# 16V2_EDA.net
KiCad netlist of a schematic drawn in EasyEDA Pro
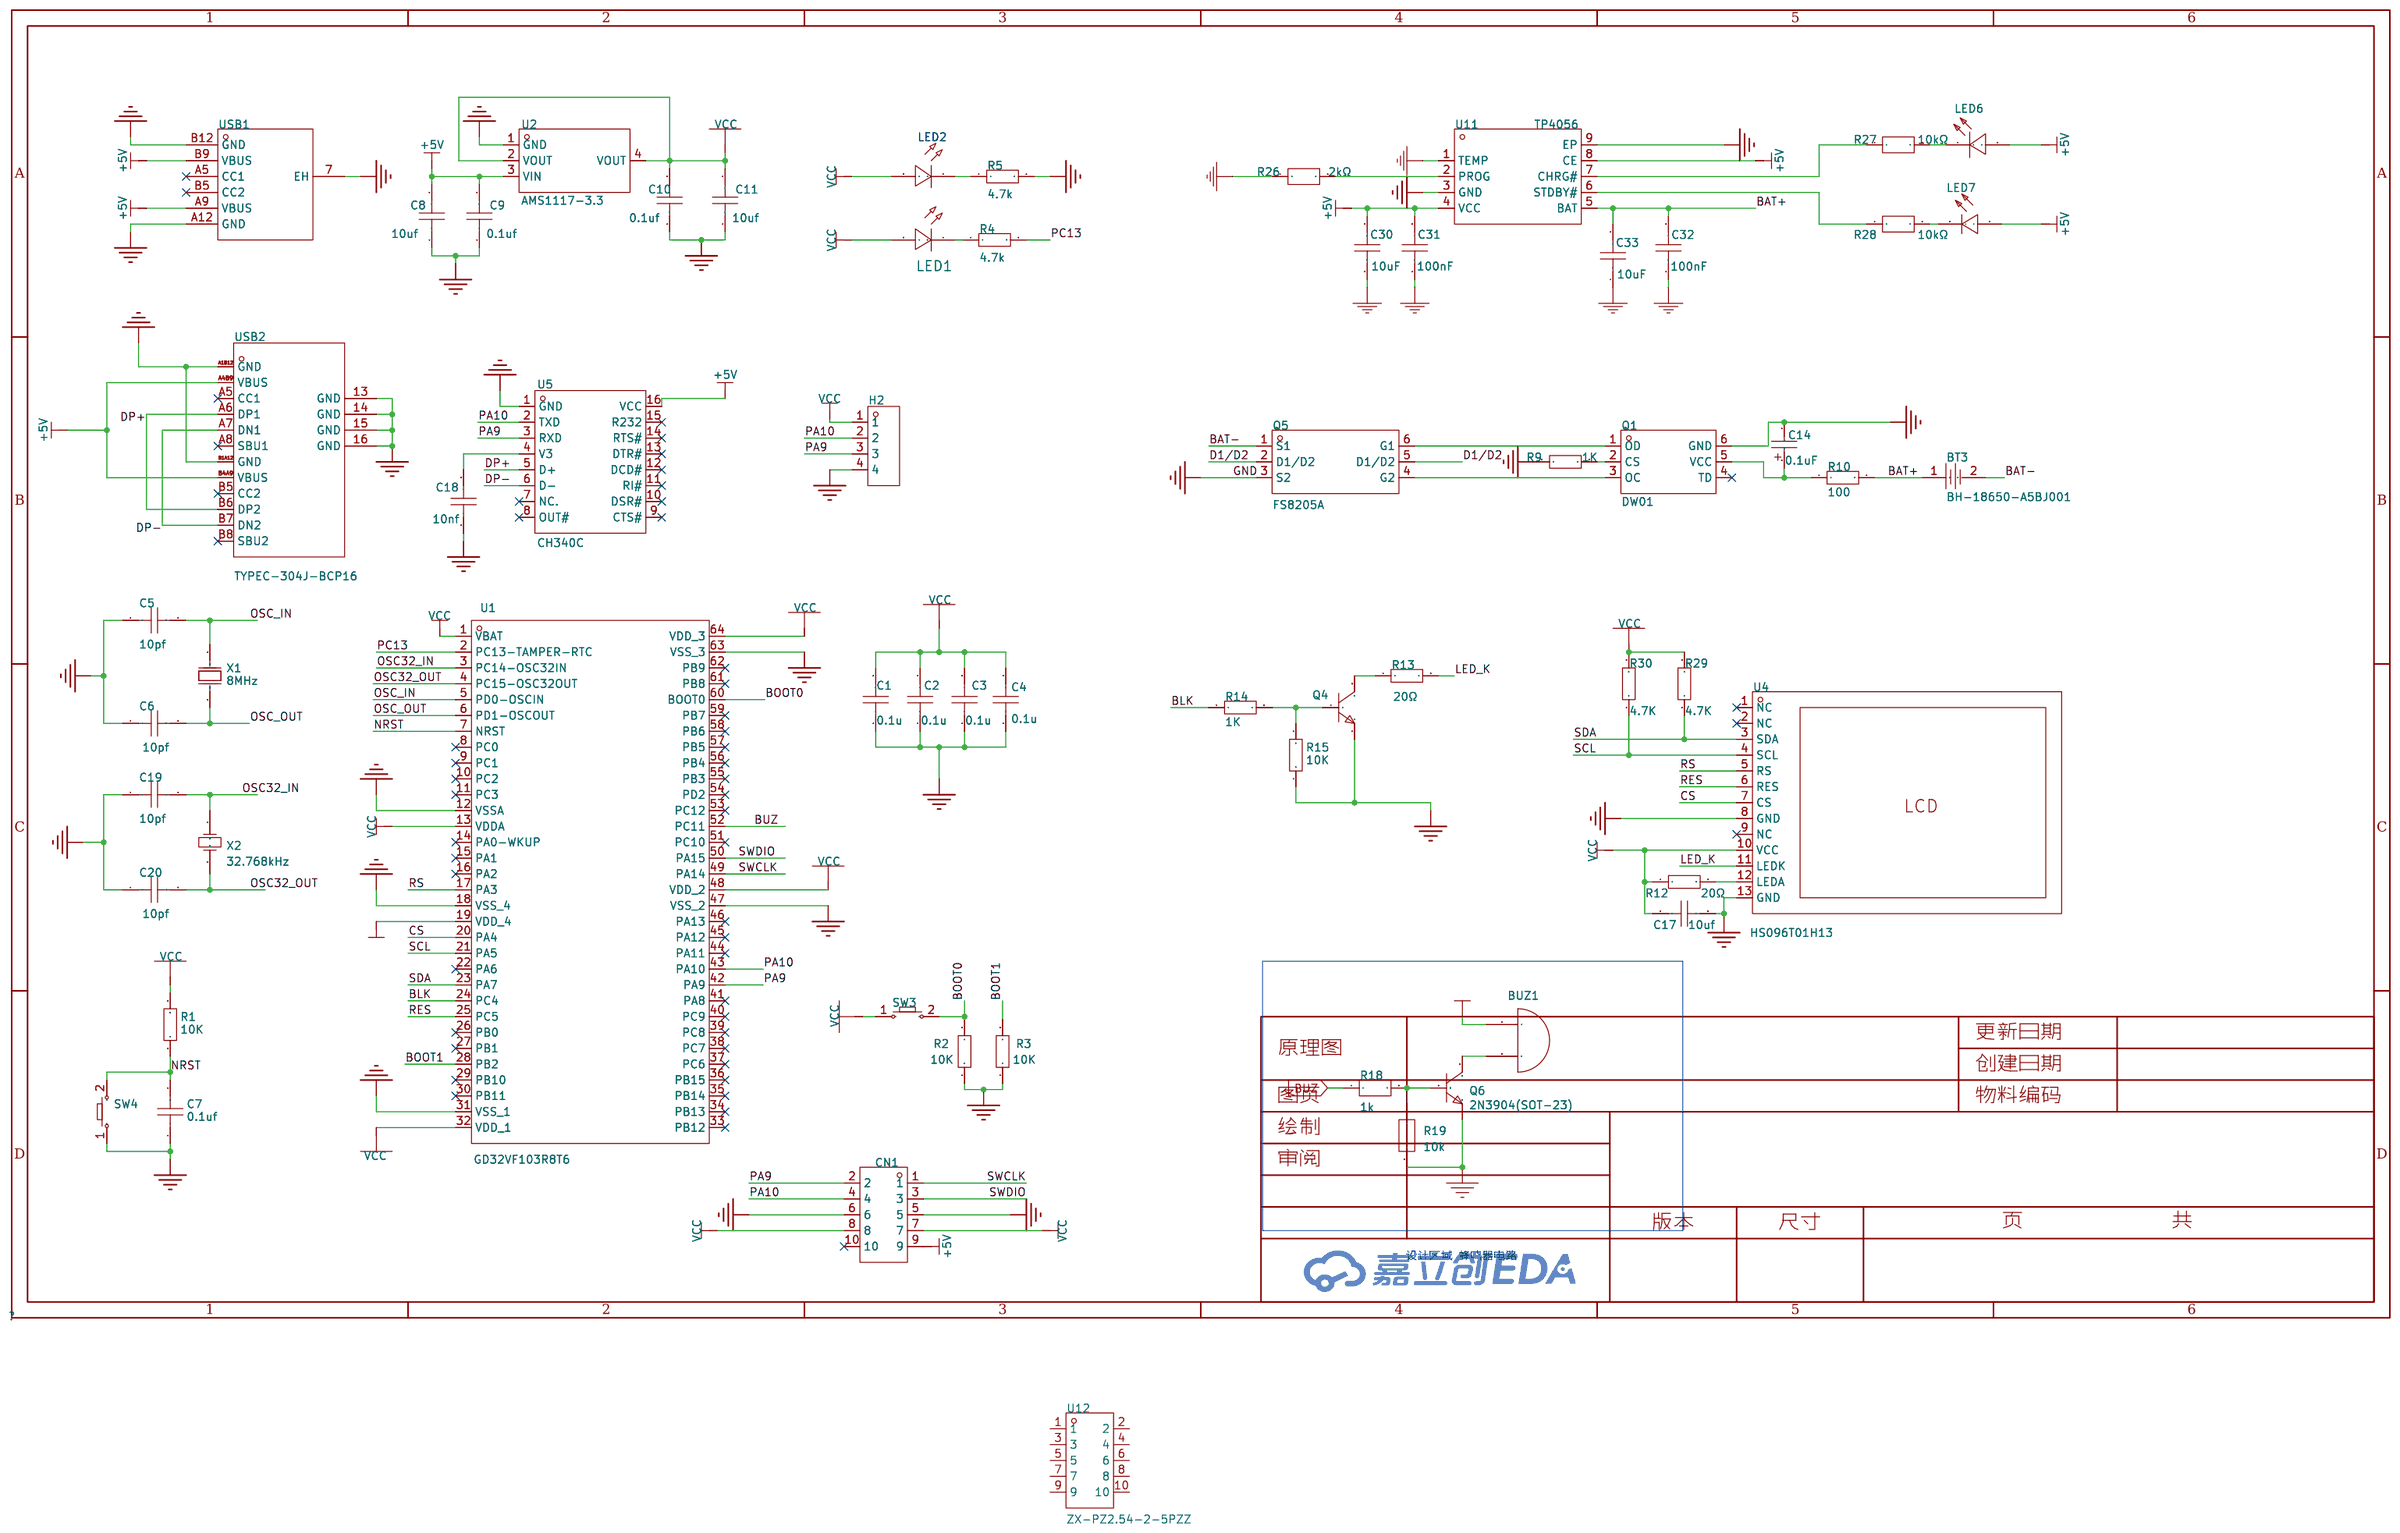
[diagram p0: schematic sheet]

(export (version "E")
  (design (tool "Eeschema 10.0.6"))
  (components
    (comp (ref "BT3")
      (value "BH-18650-A5BJ001")
      (footprint "easyedapro:BAT-TH_18650-A5BJ001")
      (description "BHNi DIP 适用电池18650电芯//电池底座/卧式DIP 电池盒/电池座 材质：PP  镀镍 ，")
      (fields (field (name "Manufacturer") "MYOUNG(美阳)"))
      (libsource (lib "easyedapro") (part "BH-18650-A5BJ001"))
    )
    (comp (ref "BUZ1") (value "BUZ1") (libsource (lib "easyedapro") (part "BUZ1")))
    (comp (ref "C1")
      (value "0.1u")
      (footprint "easyedapro:C0603")
      (libsource (lib "easyedapro") (part "capacitance"))
    )
    (comp (ref "C2")
      (value "0.1u")
      (footprint "easyedapro:C0603")
      (libsource (lib "easyedapro") (part "capacitance"))
    )
    (comp (ref "C3")
      (value "0.1u")
      (footprint "easyedapro:C0603")
      (libsource (lib "easyedapro") (part "capacitance"))
    )
    (comp (ref "C4")
      (value "0.1u")
      (footprint "easyedapro:C0603")
      (libsource (lib "easyedapro") (part "capacitance"))
    )
    (comp (ref "C5")
      (value "10pf")
      (footprint "easyedapro:C0603")
      (libsource (lib "easyedapro") (part "capacitance"))
    )
    (comp (ref "C6")
      (value "10pf")
      (footprint "easyedapro:C0603")
      (libsource (lib "easyedapro") (part "capacitance"))
    )
    (comp (ref "C7")
      (value "0.1uf")
      (footprint "easyedapro:C0603")
      (libsource (lib "easyedapro") (part "capacitance"))
    )
    (comp (ref "C8")
      (value "10uf")
      (footprint "easyedapro:C0603")
      (libsource (lib "easyedapro") (part "capacitance"))
    )
    (comp (ref "C9")
      (value "0.1uf")
      (footprint "easyedapro:C0603")
      (libsource (lib "easyedapro") (part "capacitance"))
    )
    (comp (ref "C10")
      (value "0.1uf")
      (footprint "easyedapro:C0603")
      (libsource (lib "easyedapro") (part "capacitance"))
    )
    (comp (ref "C11")
      (value "10uf")
      (footprint "easyedapro:C0603")
      (libsource (lib "easyedapro") (part "capacitance"))
    )
    (comp (ref "C14")
      (value "0.1uF")
      (footprint "easyedapro:C_Ele_SMD_3x5.4mm")
      (libsource (lib "easyedapro") (part "CAP"))
    )
    (comp (ref "C17")
      (value "10uf")
      (footprint "easyedapro:C0603")
      (libsource (lib "easyedapro") (part "capacitance"))
    )
    (comp (ref "C18")
      (value "10nf")
      (footprint "easyedapro:C0603")
      (libsource (lib "easyedapro") (part "capacitance"))
    )
    (comp (ref "C19")
      (value "10pf")
      (footprint "easyedapro:C0603")
      (libsource (lib "easyedapro") (part "capacitance"))
    )
    (comp (ref "C20")
      (value "10pf")
      (footprint "easyedapro:C0603")
      (libsource (lib "easyedapro") (part "capacitance"))
    )
    (comp (ref "C30")
      (value "10uF")
      (fields (field (name "Manufacturer") "SAMSUNG(三星)"))
      (libsource (lib "easyedapro") (part "10u"))
    )
    (comp (ref "C31")
      (value "100nF")
      (fields (field (name "Manufacturer") "YAGEO(国巨)"))
      (libsource (lib "easyedapro") (part "0.1u"))
    )
    (comp (ref "C32")
      (value "100nF")
      (fields (field (name "Manufacturer") "YAGEO(国巨)"))
      (libsource (lib "easyedapro") (part "0.1u"))
    )
    (comp (ref "C33")
      (value "10uF")
      (fields (field (name "Manufacturer") "SAMSUNG(三星)"))
      (libsource (lib "easyedapro") (part "10u"))
    )
    (comp (ref "CN1") (value "ZX-PZ2.54-2-5PZZ") (libsource (lib "easyedapro") (part "phd-2*5a_c2847737")))
    (comp (ref "H2")
      (value "2.54-1*4P反弯排针")
      (footprint "easyedapro:HDR-TH_4P-P2.54-H-M-W10.4")
      (fields (field (name "Manufacturer") "BOOMELE(博穆精密)"))
      (libsource (lib "easyedapro") (part "2.54-1*4P反弯排针"))
    )
    (comp (ref "LED1")
      (value "~")
      (footprint "easyedapro:LED_0603")
      (libsource (lib "easyedapro") (part "LED_R"))
    )
    (comp (ref "LED2")
      (value "~")
      (footprint "easyedapro:LED_0603")
      (libsource (lib "easyedapro") (part "LED_G"))
    )
    (comp (ref "LED6")
      (value "KT-0603R")
      (fields (field (name "Manufacturer") "KENTO"))
      (libsource (lib "easyedapro") (part "KT-0603R"))
    )
    (comp (ref "LED7") (value "NCD0603B1") (libsource (lib "easyedapro") (part "fc-da1608bk-470h10")))
    (comp (ref "Q1")
      (value "DW01")
      (footprint "easyedapro:SOT-23-6_L2.9-W1.6-P0.95-LS2.8-BR")
      (fields (field (name "Manufacturer") "Hottech(合科泰)"))
      (libsource (lib "easyedapro") (part "DW01"))
    )
    (comp (ref "Q4")
      (value "~")
      (footprint "easyedapro:S8050_SOT-23")
      (libsource (lib "easyedapro") (part "NPN"))
    )
    (comp (ref "Q5")
      (value "FS8205A")
      (footprint "easyedapro:SOT-23-6_L2.9-W1.6-P0.95-LS2.8-BR")
      (fields (field (name "Manufacturer") "TECH PUBLIC(台舟)"))
      (libsource (lib "easyedapro") (part "FS8205A_C2830320"))
    )
    (comp (ref "Q6")
      (value "2N3904(SOT-23)")
      (fields (field (name "Manufacturer Part") "2n3904S-RTK/PS") (field (name "Manufacturer") "KEC"))
      (libsource (lib "easyedapro") (part "2N3904(SOT-23)"))
    )
    (comp (ref "R1") (value "10K") (libsource (lib "easyedapro") (part "电阻")))
    (comp (ref "R2") (value "10K") (libsource (lib "easyedapro") (part "电阻")))
    (comp (ref "R3") (value "10K") (libsource (lib "easyedapro") (part "电阻")))
    (comp (ref "R4") (value "4.7k") (libsource (lib "easyedapro") (part "电阻")))
    (comp (ref "R5") (value "4.7k") (libsource (lib "easyedapro") (part "电阻")))
    (comp (ref "R9") (value "1K") (libsource (lib "easyedapro") (part "电阻")))
    (comp (ref "R10") (value "100") (libsource (lib "easyedapro") (part "电阻")))
    (comp (ref "R12") (value "20Ω") (libsource (lib "easyedapro") (part "电阻")))
    (comp (ref "R13") (value "20Ω") (libsource (lib "easyedapro") (part "电阻")))
    (comp (ref "R14") (value "1K") (libsource (lib "easyedapro") (part "电阻")))
    (comp (ref "R15") (value "10K") (libsource (lib "easyedapro") (part "电阻")))
    (comp (ref "R18") (value "1k") (libsource (lib "easyedapro") (part "1k")))
    (comp (ref "R19") (value "10k") (libsource (lib "easyedapro") (part "10k")))
    (comp (ref "R26")
      (value "2kΩ")
      (fields (field (name "Manufacturer") "UNI-ROYAL(厚声)"))
      (libsource (lib "easyedapro") (part "2k"))
    )
    (comp (ref "R27")
      (value "10kΩ")
      (fields (field (name "Manufacturer") "UNI-ROYAL(厚声)"))
      (libsource (lib "easyedapro") (part "10k"))
    )
    (comp (ref "R28")
      (value "10kΩ")
      (fields (field (name "Manufacturer") "UNI-ROYAL(厚声)"))
      (libsource (lib "easyedapro") (part "10k"))
    )
    (comp (ref "R29")
      (value "4.7K")
      (footprint "easyedapro:R0603")
      (libsource (lib "easyedapro") (part "电阻"))
    )
    (comp (ref "R30")
      (value "4.7K")
      (footprint "easyedapro:R0603")
      (libsource (lib "easyedapro") (part "电阻"))
    )
    (comp (ref "SW3")
      (value "~")
      (footprint "easyedapro:Key_SMD_3x4x2")
      (libsource (lib "easyedapro") (part "轻触按键x2"))
    )
    (comp (ref "SW4")
      (value "~")
      (footprint "easyedapro:Key_SMD_3x4x2")
      (libsource (lib "easyedapro") (part "轻触按键x2"))
    )
    (comp (ref "U1")
      (value "GD32VF103R8T6")
      (footprint "easyedapro:LQFP-64_L10.0-W10.0-P0.50-LS12.0-BL")
      (description "CPU内核:RISC-V;程序存储容量:64KB;RAM总容量:20KB;GPIO端口数量:51;工作电压范围:-;CPU最大主频:108MHz;程序存储器类型:FLASH;")
      (fields (field (name "Manufacturer") "GigaDevice(兆易创新)"))
      (libsource (lib "easyedapro") (part "GD32VF103R8T6"))
    )
    (comp (ref "U2")
      (value "AMS1117-3.3")
      (footprint "easyedapro:SOT-223-3_L6.5-W3.4-P2.30-LS7.0-BR")
      (description "输出类型:固定;最大输入电压:-;输出电压:3.3V;最大输出电流:1A;电源纹波抑制比(PSRR):72dB@(120Hz);输出极性:正极;")
      (fields (field (name "Manufacturer") "AMS"))
      (libsource (lib "easyedapro") (part "AMS1117-3.3"))
    )
    (comp (ref "U4")
      (value "HS096T01H13")
      (footprint "easyedapro:LCD-SMD_HS096T01H13")
      (description "主控芯片:ST7735;尺寸(inch):0.96;")
      (fields (field (name "Manufacturer") "HS(汉昇)"))
      (libsource (lib "easyedapro") (part "HS096T01H13"))
    )
    (comp (ref "U5")
      (value "CH340C")
      (footprint "easyedapro:SOP-16_L10.0-W3.9-P1.27-LS6.0-BL")
      (description "应用功能:收发器;接口协议:USB 2.0;数据速率:2Mbps;")
      (fields (field (name "Manufacturer") "WCH(南京沁恒)"))
      (libsource (lib "easyedapro") (part "CH340C"))
    )
    (comp (ref "U11")
      (value "TP4056")
      (fields (field (name "Manufacturer") "UMW(友台半导体)"))
      (libsource (lib "easyedapro") (part "TP4056_C725790"))
    )
    (comp (ref "U12")
      (value "ZX-PZ2.54-2-5PZZ")
      (footprint "easyedapro:HDR-TH_10P-P2.54-V-M-R2-C5-S2.54")
      (fields (field (name "Manufacturer") "Megastar(兆星)"))
      (libsource (lib "easyedapro") (part "ZX-PZ2.54-2-5PZZ"))
    )
    (comp (ref "USB1")
      (value "TYPE-C 6P")
      (footprint "easyedapro:TYPE-C-SMD_TYPE-C-6P")
      (description "连接器类型:Type-C;标准:-;公母:母;端口数量:1;触点数量:6P;安装方式:卧贴;额定电流 - 电源:-;工作温度范围:-40°C~+85°C;")
      (fields (field (name "Manufacturer") "SHOU HAN(首韩)"))
      (libsource (lib "easyedapro") (part "TYPE-C 6P"))
    )
    (comp (ref "USB2")
      (value "TYPEC-304J-BCP16")
      (footprint "easyedapro:USB-C-SMD_TYPEC-304J-BCP16")
      (fields (field (name "Manufacturer") "XUNPU(讯普)"))
      (libsource (lib "easyedapro") (part "TYPEC-304J-BCP16"))
    )
    (comp (ref "X1")
      (value "8MHz")
      (footprint "easyedapro:CRYSTAL-SMD_L11.5-W4.8-LS12.7")
      (description "晶振类型:贴片晶振;频率:8MHz;常温频差:±20ppm;外接负载电容:20pF;频率稳定度(全温):±30ppm;")
      (fields (field (name "Manufacturer Part") "X49SM8MSD2SC") (field (name "Manufacturer") "YXC(扬兴晶振)"))
      (libsource (lib "easyedapro") (part "X49SM8MSD2SC"))
    )
    (comp (ref "X2")
      (value "32.768kHz")
      (footprint "easyedapro:OSC-TH_BD3.1-P0.8-D0.3")
      (description "晶振类型:直插晶振;频率:32.768kHz;常温频差:±10ppm;外接负载电容:12.5pF;频率稳定度(全温):-;")
      (fields (field (name "Manufacturer Part") "X308032768KGB2SC") (field (name "Manufacturer") "YXC(扬兴晶振)"))
      (libsource (lib "easyedapro") (part "X308032768KGB2SC"))
    )
  )
  (nets
    (net (code "1") (name "+5V") (class "Default")
      (node (ref "C30") (pin "2") (pinfunction "2_2") (pintype "unspecified"))
      (node (ref "C31") (pin "2") (pinfunction "2_2") (pintype "unspecified"))
      (node (ref "C8") (pin "2") (pinfunction "2_2") (pintype "input"))
      (node (ref "C9") (pin "2") (pinfunction "2_2") (pintype "input"))
      (node (ref "CN1") (pin "9") (pinfunction "9_9") (pintype "unspecified"))
      (node (ref "LED6") (pin "2") (pinfunction "A_2") (pintype "unspecified"))
      (node (ref "LED7") (pin "2") (pinfunction "+_2") (pintype "input"))
      (node (ref "U11") (pin "4") (pinfunction "VCC_4") (pintype "unspecified"))
      (node (ref "U11") (pin "8") (pinfunction "CE_8") (pintype "unspecified"))
      (node (ref "U2") (pin "3") (pinfunction "VIN_3") (pintype "unspecified"))
      (node (ref "U5") (pin "16") (pinfunction "VCC_16") (pintype "unspecified"))
      (node (ref "USB1") (pin "A9") (pinfunction "VBUS_A9") (pintype "unspecified"))
      (node (ref "USB1") (pin "B9") (pinfunction "VBUS_B9") (pintype "unspecified"))
      (node (ref "USB2") (pin "A4B9") (pinfunction "VBUS_A4B9") (pintype "unspecified"))
      (node (ref "USB2") (pin "B4A9") (pinfunction "VBUS_B4A9") (pintype "unspecified"))
    )
    (net (code "2") (name "/BAT+") (class "Default")
      (node (ref "BT3") (pin "1") (pinfunction "1_1") (pintype "input"))
      (node (ref "C32") (pin "2") (pinfunction "2_2") (pintype "unspecified"))
      (node (ref "C33") (pin "2") (pinfunction "2_2") (pintype "unspecified"))
      (node (ref "R10") (pin "2") (pinfunction "2_2") (pintype "input"))
      (node (ref "U11") (pin "5") (pinfunction "BAT_5") (pintype "unspecified"))
    )
    (net (code "3") (name "/BAT-") (class "Default")
      (node (ref "BT3") (pin "2") (pinfunction "2_2") (pintype "input"))
      (node (ref "Q5") (pin "1") (pinfunction "S1_1") (pintype "unspecified"))
    )
    (net (code "4") (name "/BLK") (class "Default")
      (node (ref "R14") (pin "1") (pinfunction "1_1") (pintype "input"))
      (node (ref "U1") (pin "24") (pinfunction "PC4_24") (pintype "input"))
    )
    (net (code "5") (name "/BOOT0") (class "Default")
      (node (ref "R2") (pin "2") (pinfunction "2_2") (pintype "input"))
      (node (ref "SW3") (pin "2") (pinfunction "2_2") (pintype "input"))
      (node (ref "U1") (pin "60") (pinfunction "BOOT0_60") (pintype "input"))
    )
    (net (code "6") (name "/BOOT1") (class "Default")
      (node (ref "R3") (pin "2") (pinfunction "2_2") (pintype "input"))
      (node (ref "U1") (pin "28") (pinfunction "PB2_28") (pintype "input"))
    )
    (net (code "7") (name "/CS") (class "Default")
      (node (ref "U1") (pin "20") (pinfunction "PA4_20") (pintype "input"))
      (node (ref "U4") (pin "7") (pinfunction "CS_7") (pintype "unspecified"))
    )
    (net (code "8") (name "/D1{slash}D2") (class "Default")
      (node (ref "Q5") (pin "2") (pinfunction "D1/D2_2") (pintype "unspecified"))
      (node (ref "Q5") (pin "5") (pinfunction "D1/D2_5") (pintype "unspecified"))
    )
    (net (code "9") (name "/DP+") (class "Default")
      (node (ref "U5") (pin "5") (pinfunction "D+_5") (pintype "unspecified"))
      (node (ref "USB2") (pin "A6") (pinfunction "DP1_A6") (pintype "unspecified"))
      (node (ref "USB2") (pin "B6") (pinfunction "DP2_B6") (pintype "unspecified"))
    )
    (net (code "10") (name "/DP-") (class "Default")
      (node (ref "U5") (pin "6") (pinfunction "D-_6") (pintype "unspecified"))
      (node (ref "USB2") (pin "A7") (pinfunction "DN1_A7") (pintype "unspecified"))
      (node (ref "USB2") (pin "B7") (pinfunction "DN2_B7") (pintype "unspecified"))
    )
    (net (code "11") (name "/LED_K") (class "Default")
      (node (ref "R13") (pin "2") (pinfunction "2_2") (pintype "input"))
      (node (ref "U4") (pin "11") (pinfunction "LEDK_11") (pintype "unspecified"))
    )
    (net (code "12") (name "/NRST") (class "Default")
      (node (ref "C7") (pin "2") (pinfunction "2_2") (pintype "input"))
      (node (ref "R1") (pin "1") (pinfunction "1_1") (pintype "input"))
      (node (ref "SW4") (pin "2") (pinfunction "2_2") (pintype "input"))
      (node (ref "U1") (pin "7") (pinfunction "NRST_7") (pintype "input"))
    )
    (net (code "13") (name "/OSC32_IN") (class "Default")
      (node (ref "C19") (pin "2") (pinfunction "2_2") (pintype "input"))
      (node (ref "U1") (pin "3") (pinfunction "PC14-OSC32IN_3") (pintype "input"))
      (node (ref "X2") (pin "1") (pinfunction "OSC1_1") (pintype "unspecified"))
    )
    (net (code "14") (name "/OSC32_OUT") (class "Default")
      (node (ref "C20") (pin "2") (pinfunction "2_2") (pintype "input"))
      (node (ref "U1") (pin "4") (pinfunction "PC15-OSC32OUT_4") (pintype "input"))
      (node (ref "X2") (pin "2") (pinfunction "OSC2_2") (pintype "unspecified"))
    )
    (net (code "15") (name "/OSC_IN") (class "Default")
      (node (ref "C5") (pin "2") (pinfunction "2_2") (pintype "input"))
      (node (ref "U1") (pin "5") (pinfunction "PD0-OSCIN_5") (pintype "input"))
      (node (ref "X1") (pin "1") (pinfunction "OSC1_1") (pintype "input"))
    )
    (net (code "16") (name "/OSC_OUT") (class "Default")
      (node (ref "C6") (pin "2") (pinfunction "2_2") (pintype "input"))
      (node (ref "U1") (pin "6") (pinfunction "PD1-OSCOUT_6") (pintype "input"))
      (node (ref "X1") (pin "2") (pinfunction "OSC2_2") (pintype "input"))
    )
    (net (code "17") (name "/PA9") (class "Default")
      (node (ref "CN1") (pin "2") (pinfunction "2_2") (pintype "unspecified"))
      (node (ref "H2") (pin "3") (pinfunction "3_3") (pintype "unspecified"))
      (node (ref "U1") (pin "42") (pinfunction "PA9_42") (pintype "input"))
      (node (ref "U5") (pin "3") (pinfunction "RXD_3") (pintype "unspecified"))
    )
    (net (code "18") (name "/PA10") (class "Default")
      (node (ref "CN1") (pin "4") (pinfunction "4_4") (pintype "unspecified"))
      (node (ref "H2") (pin "2") (pinfunction "2_2") (pintype "unspecified"))
      (node (ref "U1") (pin "43") (pinfunction "PA10_43") (pintype "input"))
      (node (ref "U5") (pin "2") (pinfunction "TXD_2") (pintype "unspecified"))
    )
    (net (code "19") (name "/PC13") (class "Default")
      (node (ref "R4") (pin "2") (pinfunction "2_2") (pintype "input"))
      (node (ref "U1") (pin "2") (pinfunction "PC13-TAMPER-RTC_2") (pintype "input"))
    )
    (net (code "20") (name "/RES") (class "Default")
      (node (ref "U1") (pin "25") (pinfunction "PC5_25") (pintype "input"))
      (node (ref "U4") (pin "6") (pinfunction "RES_6") (pintype "unspecified"))
    )
    (net (code "21") (name "/RS") (class "Default")
      (node (ref "U1") (pin "17") (pinfunction "PA3_17") (pintype "input"))
      (node (ref "U4") (pin "5") (pinfunction "RS_5") (pintype "unspecified"))
    )
    (net (code "22") (name "/SCL") (class "Default")
      (node (ref "R30") (pin "1") (pinfunction "1_1") (pintype "input"))
      (node (ref "U1") (pin "21") (pinfunction "PA5_21") (pintype "input"))
      (node (ref "U4") (pin "4") (pinfunction "SCL_4") (pintype "unspecified"))
    )
    (net (code "23") (name "/SDA") (class "Default")
      (node (ref "R29") (pin "1") (pinfunction "1_1") (pintype "input"))
      (node (ref "U1") (pin "23") (pinfunction "PA7_23") (pintype "input"))
      (node (ref "U4") (pin "3") (pinfunction "SDA_3") (pintype "unspecified"))
    )
    (net (code "24") (name "/SWCLK") (class "Default")
      (node (ref "CN1") (pin "1") (pinfunction "1_1") (pintype "unspecified"))
      (node (ref "U1") (pin "49") (pinfunction "PA14_49") (pintype "input"))
    )
    (net (code "25") (name "/SWDIO") (class "Default")
      (node (ref "CN1") (pin "3") (pinfunction "3_3") (pintype "unspecified"))
      (node (ref "U1") (pin "50") (pinfunction "PA15_50") (pintype "input"))
    )
    (net (code "26") (name "BUZ") (class "Default")
      (node (ref "R18") (pin "1") (pinfunction "1_1") (pintype "input"))
      (node (ref "U1") (pin "52") (pinfunction "PC11_52") (pintype "input"))
    )
    (net (code "27") (name "GND") (class "Default")
      (node (ref "C1") (pin "1") (pinfunction "1_1") (pintype "input"))
      (node (ref "C10") (pin "1") (pinfunction "1_1") (pintype "input"))
      (node (ref "C11") (pin "1") (pinfunction "1_1") (pintype "input"))
      (node (ref "C14") (pin "2") (pinfunction "2_2") (pintype "input"))
      (node (ref "C17") (pin "2") (pinfunction "2_2") (pintype "input"))
      (node (ref "C18") (pin "1") (pinfunction "1_1") (pintype "input"))
      (node (ref "C19") (pin "1") (pinfunction "1_1") (pintype "input"))
      (node (ref "C2") (pin "1") (pinfunction "1_1") (pintype "input"))
      (node (ref "C20") (pin "1") (pinfunction "1_1") (pintype "input"))
      (node (ref "C3") (pin "1") (pinfunction "1_1") (pintype "input"))
      (node (ref "C30") (pin "1") (pinfunction "1_1") (pintype "unspecified"))
      (node (ref "C31") (pin "1") (pinfunction "1_1") (pintype "unspecified"))
      (node (ref "C32") (pin "1") (pinfunction "1_1") (pintype "unspecified"))
      (node (ref "C33") (pin "1") (pinfunction "1_1") (pintype "unspecified"))
      (node (ref "C4") (pin "1") (pinfunction "1_1") (pintype "input"))
      (node (ref "C5") (pin "1") (pinfunction "1_1") (pintype "input"))
      (node (ref "C6") (pin "1") (pinfunction "1_1") (pintype "input"))
      (node (ref "C7") (pin "1") (pinfunction "1_1") (pintype "input"))
      (node (ref "C8") (pin "1") (pinfunction "1_1") (pintype "input"))
      (node (ref "C9") (pin "1") (pinfunction "1_1") (pintype "input"))
      (node (ref "CN1") (pin "5") (pinfunction "5_5") (pintype "unspecified"))
      (node (ref "CN1") (pin "6") (pinfunction "6_6") (pintype "unspecified"))
      (node (ref "H2") (pin "4") (pinfunction "4_4") (pintype "unspecified"))
      (node (ref "Q1") (pin "6") (pinfunction "GND_6") (pintype "input"))
      (node (ref "Q4") (pin "2") (pinfunction "2_2") (pintype "unspecified"))
      (node (ref "Q5") (pin "3") (pinfunction "S2_3") (pintype "unspecified"))
      (node (ref "Q6") (pin "1") (pinfunction "E_1") (pintype "input"))
      (node (ref "R15") (pin "1") (pinfunction "1_1") (pintype "input"))
      (node (ref "R19") (pin "2") (pinfunction "2_2") (pintype "unspecified"))
      (node (ref "R2") (pin "1") (pinfunction "1_1") (pintype "input"))
      (node (ref "R26") (pin "1") (pinfunction "1_1") (pintype "unspecified"))
      (node (ref "R3") (pin "1") (pinfunction "1_1") (pintype "input"))
      (node (ref "R5") (pin "2") (pinfunction "2_2") (pintype "input"))
      (node (ref "R9") (pin "1") (pinfunction "1_1") (pintype "input"))
      (node (ref "SW4") (pin "1") (pinfunction "1_1") (pintype "input"))
      (node (ref "U1") (pin "12") (pinfunction "VSSA_12") (pintype "input"))
      (node (ref "U1") (pin "18") (pinfunction "VSS_4_18") (pintype "input"))
      (node (ref "U1") (pin "31") (pinfunction "VSS_1_31") (pintype "input"))
      (node (ref "U1") (pin "47") (pinfunction "VSS_2_47") (pintype "input"))
      (node (ref "U1") (pin "63") (pinfunction "VSS_3_63") (pintype "input"))
      (node (ref "U11") (pin "1") (pinfunction "TEMP_1") (pintype "unspecified"))
      (node (ref "U11") (pin "3") (pinfunction "GND_3") (pintype "unspecified"))
      (node (ref "U11") (pin "9") (pinfunction "EP_9") (pintype "unspecified"))
      (node (ref "U2") (pin "1") (pinfunction "GND_1") (pintype "unspecified"))
      (node (ref "U4") (pin "13") (pinfunction "GND_13") (pintype "unspecified"))
      (node (ref "U4") (pin "8") (pinfunction "GND_8") (pintype "unspecified"))
      (node (ref "U5") (pin "1") (pinfunction "GND_1") (pintype "unspecified"))
      (node (ref "USB1") (pin "7") (pinfunction "EH_7") (pintype "unspecified"))
      (node (ref "USB1") (pin "A12") (pinfunction "GND_A12") (pintype "unspecified"))
      (node (ref "USB1") (pin "B12") (pinfunction "GND_B12") (pintype "unspecified"))
      (node (ref "USB2") (pin "13") (pinfunction "GND_13") (pintype "unspecified"))
      (node (ref "USB2") (pin "14") (pinfunction "GND_14") (pintype "unspecified"))
      (node (ref "USB2") (pin "15") (pinfunction "GND_15") (pintype "unspecified"))
      (node (ref "USB2") (pin "16") (pinfunction "GND_16") (pintype "unspecified"))
      (node (ref "USB2") (pin "A1B12") (pinfunction "GND_A1B12") (pintype "unspecified"))
      (node (ref "USB2") (pin "B1A12") (pinfunction "GND_B1A12") (pintype "unspecified"))
    )
    (net (code "28") (name "Net-(BUZ1-B)") (class "Default")
      (node (ref "BUZ1") (pin "2") (pinfunction "B_2") (pintype "input"))
      (node (ref "Q6") (pin "3") (pinfunction "C_3") (pintype "input"))
    )
    (net (code "29") (name "Net-(LED1-C)") (class "Default")
      (node (ref "LED1") (pin "1") (pinfunction "C_1") (pintype "input"))
      (node (ref "R4") (pin "1") (pinfunction "1_1") (pintype "input"))
    )
    (net (code "30") (name "Net-(LED2-C)") (class "Default")
      (node (ref "LED2") (pin "1") (pinfunction "C_1") (pintype "input"))
      (node (ref "R5") (pin "1") (pinfunction "1_1") (pintype "input"))
    )
    (net (code "31") (name "Net-(LED6-K)") (class "Default")
      (node (ref "LED6") (pin "1") (pinfunction "K_1") (pintype "unspecified"))
      (node (ref "R27") (pin "2") (pinfunction "2_2") (pintype "unspecified"))
    )
    (net (code "32") (name "Net-(LED7--)") (class "Default")
      (node (ref "LED7") (pin "1") (pinfunction "-_1") (pintype "input"))
      (node (ref "R28") (pin "2") (pinfunction "2_2") (pintype "unspecified"))
    )
    (net (code "33") (name "Net-(Q1-CS)") (class "Default")
      (node (ref "Q1") (pin "2") (pinfunction "CS_2") (pintype "input"))
      (node (ref "R9") (pin "2") (pinfunction "2_2") (pintype "input"))
    )
    (net (code "34") (name "Net-(Q1-OC)") (class "Default")
      (node (ref "Q1") (pin "3") (pinfunction "OC_3") (pintype "input"))
      (node (ref "Q5") (pin "4") (pinfunction "G2_4") (pintype "unspecified"))
    )
    (net (code "35") (name "Net-(Q1-OD)") (class "Default")
      (node (ref "Q1") (pin "1") (pinfunction "OD_1") (pintype "input"))
      (node (ref "Q5") (pin "6") (pinfunction "G1_6") (pintype "unspecified"))
    )
    (net (code "36") (name "Net-(Q1-VCC)") (class "Default")
      (node (ref "C14") (pin "1") (pinfunction "1_1") (pintype "input"))
      (node (ref "Q1") (pin "5") (pinfunction "VCC_5") (pintype "input"))
      (node (ref "R10") (pin "1") (pinfunction "1_1") (pintype "input"))
    )
    (net (code "37") (name "Net-(Q4-Pad1)") (class "Default")
      (node (ref "Q4") (pin "1") (pinfunction "1_1") (pintype "unspecified"))
      (node (ref "R14") (pin "2") (pinfunction "2_2") (pintype "input"))
      (node (ref "R15") (pin "2") (pinfunction "2_2") (pintype "input"))
    )
    (net (code "38") (name "Net-(Q4-Pad3)") (class "Default")
      (node (ref "Q4") (pin "3") (pinfunction "3_3") (pintype "unspecified"))
      (node (ref "R13") (pin "1") (pinfunction "1_1") (pintype "input"))
    )
    (net (code "39") (name "Net-(Q6-B)") (class "Default")
      (node (ref "Q6") (pin "2") (pinfunction "B_2") (pintype "input"))
      (node (ref "R18") (pin "2") (pinfunction "2_2") (pintype "input"))
      (node (ref "R19") (pin "1") (pinfunction "1_1") (pintype "unspecified"))
    )
    (net (code "40") (name "Net-(U4-LEDA)") (class "Default")
      (node (ref "R12") (pin "2") (pinfunction "2_2") (pintype "input"))
      (node (ref "U4") (pin "12") (pinfunction "LEDA_12") (pintype "unspecified"))
    )
    (net (code "41") (name "Net-(U5-V3)") (class "Default")
      (node (ref "C18") (pin "2") (pinfunction "2_2") (pintype "input"))
      (node (ref "U5") (pin "4") (pinfunction "V3_4") (pintype "unspecified"))
    )
    (net (code "42") (name "Net-(U11-CHRG#)") (class "Default")
      (node (ref "R27") (pin "1") (pinfunction "1_1") (pintype "unspecified"))
      (node (ref "U11") (pin "7") (pinfunction "CHRG#_7") (pintype "unspecified"))
    )
    (net (code "43") (name "Net-(U11-PROG)") (class "Default")
      (node (ref "R26") (pin "2") (pinfunction "2_2") (pintype "unspecified"))
      (node (ref "U11") (pin "2") (pinfunction "PROG_2") (pintype "unspecified"))
    )
    (net (code "44") (name "Net-(U11-STDBY#)") (class "Default")
      (node (ref "R28") (pin "1") (pinfunction "1_1") (pintype "unspecified"))
      (node (ref "U11") (pin "6") (pinfunction "STDBY#_6") (pintype "unspecified"))
    )
    (net (code "45") (name "VCC") (class "Default")
      (node (ref "BUZ1") (pin "1") (pinfunction "A_1") (pintype "input"))
      (node (ref "C1") (pin "2") (pinfunction "2_2") (pintype "input"))
      (node (ref "C10") (pin "2") (pinfunction "2_2") (pintype "input"))
      (node (ref "C11") (pin "2") (pinfunction "2_2") (pintype "input"))
      (node (ref "C17") (pin "1") (pinfunction "1_1") (pintype "input"))
      (node (ref "C2") (pin "2") (pinfunction "2_2") (pintype "input"))
      (node (ref "C3") (pin "2") (pinfunction "2_2") (pintype "input"))
      (node (ref "C4") (pin "2") (pinfunction "2_2") (pintype "input"))
      (node (ref "CN1") (pin "7") (pinfunction "7_7") (pintype "unspecified"))
      (node (ref "CN1") (pin "8") (pinfunction "8_8") (pintype "unspecified"))
      (node (ref "H2") (pin "1") (pinfunction "1_1") (pintype "unspecified"))
      (node (ref "LED1") (pin "2") (pinfunction "A_2") (pintype "input"))
      (node (ref "LED2") (pin "2") (pinfunction "A_2") (pintype "input"))
      (node (ref "R1") (pin "2") (pinfunction "2_2") (pintype "input"))
      (node (ref "R12") (pin "1") (pinfunction "1_1") (pintype "input"))
      (node (ref "R29") (pin "2") (pinfunction "2_2") (pintype "input"))
      (node (ref "R30") (pin "2") (pinfunction "2_2") (pintype "input"))
      (node (ref "SW3") (pin "1") (pinfunction "1_1") (pintype "input"))
      (node (ref "U1") (pin "1") (pinfunction "VBAT_1") (pintype "input"))
      (node (ref "U1") (pin "13") (pinfunction "VDDA_13") (pintype "input"))
      (node (ref "U1") (pin "19") (pinfunction "VDD_4_19") (pintype "input"))
      (node (ref "U1") (pin "32") (pinfunction "VDD_1_32") (pintype "input"))
      (node (ref "U1") (pin "48") (pinfunction "VDD_2_48") (pintype "input"))
      (node (ref "U1") (pin "64") (pinfunction "VDD_3_64") (pintype "input"))
      (node (ref "U2") (pin "2") (pinfunction "VOUT_2") (pintype "unspecified"))
      (node (ref "U2") (pin "4") (pinfunction "VOUT_4") (pintype "unspecified"))
      (node (ref "U4") (pin "10") (pinfunction "VCC_10") (pintype "unspecified"))
    )
    (net (code "46") (name "unconnected-(CN1-Pad10)") (class "Default")
      (node (ref "CN1") (pin "10") (pinfunction "10_10") (pintype "unspecified+no_connect"))
    )
    (net (code "47") (name "unconnected-(Q1-TD-Pad4)") (class "Default")
      (node (ref "Q1") (pin "4") (pinfunction "TD_4") (pintype "input+no_connect"))
    )
    (net (code "48") (name "unconnected-(U1-PA0-WKUP-Pad14)") (class "Default")
      (node (ref "U1") (pin "14") (pinfunction "PA0-WKUP_14") (pintype "input+no_connect"))
    )
    (net (code "49") (name "unconnected-(U1-PA1-Pad15)") (class "Default")
      (node (ref "U1") (pin "15") (pinfunction "PA1_15") (pintype "input+no_connect"))
    )
    (net (code "50") (name "unconnected-(U1-PA2-Pad16)") (class "Default")
      (node (ref "U1") (pin "16") (pinfunction "PA2_16") (pintype "input+no_connect"))
    )
    (net (code "51") (name "unconnected-(U1-PA6-Pad22)") (class "Default")
      (node (ref "U1") (pin "22") (pinfunction "PA6_22") (pintype "input+no_connect"))
    )
    (net (code "52") (name "unconnected-(U1-PA8-Pad41)") (class "Default")
      (node (ref "U1") (pin "41") (pinfunction "PA8_41") (pintype "input+no_connect"))
    )
    (net (code "53") (name "unconnected-(U1-PA11-Pad44)") (class "Default")
      (node (ref "U1") (pin "44") (pinfunction "PA11_44") (pintype "input+no_connect"))
    )
    (net (code "54") (name "unconnected-(U1-PA12-Pad45)") (class "Default")
      (node (ref "U1") (pin "45") (pinfunction "PA12_45") (pintype "input+no_connect"))
    )
    (net (code "55") (name "unconnected-(U1-PA13-Pad46)") (class "Default")
      (node (ref "U1") (pin "46") (pinfunction "PA13_46") (pintype "input+no_connect"))
    )
    (net (code "56") (name "unconnected-(U1-PB0-Pad26)") (class "Default")
      (node (ref "U1") (pin "26") (pinfunction "PB0_26") (pintype "input+no_connect"))
    )
    (net (code "57") (name "unconnected-(U1-PB1-Pad27)") (class "Default")
      (node (ref "U1") (pin "27") (pinfunction "PB1_27") (pintype "input+no_connect"))
    )
    (net (code "58") (name "unconnected-(U1-PB3-Pad55)") (class "Default")
      (node (ref "U1") (pin "55") (pinfunction "PB3_55") (pintype "input+no_connect"))
    )
    (net (code "59") (name "unconnected-(U1-PB4-Pad56)") (class "Default")
      (node (ref "U1") (pin "56") (pinfunction "PB4_56") (pintype "input+no_connect"))
    )
    (net (code "60") (name "unconnected-(U1-PB5-Pad57)") (class "Default")
      (node (ref "U1") (pin "57") (pinfunction "PB5_57") (pintype "input+no_connect"))
    )
    (net (code "61") (name "unconnected-(U1-PB6-Pad58)") (class "Default")
      (node (ref "U1") (pin "58") (pinfunction "PB6_58") (pintype "input+no_connect"))
    )
    (net (code "62") (name "unconnected-(U1-PB7-Pad59)") (class "Default")
      (node (ref "U1") (pin "59") (pinfunction "PB7_59") (pintype "input+no_connect"))
    )
    (net (code "63") (name "unconnected-(U1-PB8-Pad61)") (class "Default")
      (node (ref "U1") (pin "61") (pinfunction "PB8_61") (pintype "input+no_connect"))
    )
    (net (code "64") (name "unconnected-(U1-PB9-Pad62)") (class "Default")
      (node (ref "U1") (pin "62") (pinfunction "PB9_62") (pintype "input+no_connect"))
    )
    (net (code "65") (name "unconnected-(U1-PB10-Pad29)") (class "Default")
      (node (ref "U1") (pin "29") (pinfunction "PB10_29") (pintype "input+no_connect"))
    )
    (net (code "66") (name "unconnected-(U1-PB11-Pad30)") (class "Default")
      (node (ref "U1") (pin "30") (pinfunction "PB11_30") (pintype "input+no_connect"))
    )
    (net (code "67") (name "unconnected-(U1-PB12-Pad33)") (class "Default")
      (node (ref "U1") (pin "33") (pinfunction "PB12_33") (pintype "input+no_connect"))
    )
    (net (code "68") (name "unconnected-(U1-PB13-Pad34)") (class "Default")
      (node (ref "U1") (pin "34") (pinfunction "PB13_34") (pintype "input+no_connect"))
    )
    (net (code "69") (name "unconnected-(U1-PB14-Pad35)") (class "Default")
      (node (ref "U1") (pin "35") (pinfunction "PB14_35") (pintype "input+no_connect"))
    )
    (net (code "70") (name "unconnected-(U1-PB15-Pad36)") (class "Default")
      (node (ref "U1") (pin "36") (pinfunction "PB15_36") (pintype "input+no_connect"))
    )
    (net (code "71") (name "unconnected-(U1-PC0-Pad8)") (class "Default")
      (node (ref "U1") (pin "8") (pinfunction "PC0_8") (pintype "input+no_connect"))
    )
    (net (code "72") (name "unconnected-(U1-PC1-Pad9)") (class "Default")
      (node (ref "U1") (pin "9") (pinfunction "PC1_9") (pintype "input+no_connect"))
    )
    (net (code "73") (name "unconnected-(U1-PC2-Pad10)") (class "Default")
      (node (ref "U1") (pin "10") (pinfunction "PC2_10") (pintype "input+no_connect"))
    )
    (net (code "74") (name "unconnected-(U1-PC3-Pad11)") (class "Default")
      (node (ref "U1") (pin "11") (pinfunction "PC3_11") (pintype "input+no_connect"))
    )
    (net (code "75") (name "unconnected-(U1-PC6-Pad37)") (class "Default")
      (node (ref "U1") (pin "37") (pinfunction "PC6_37") (pintype "input+no_connect"))
    )
    (net (code "76") (name "unconnected-(U1-PC7-Pad38)") (class "Default")
      (node (ref "U1") (pin "38") (pinfunction "PC7_38") (pintype "input+no_connect"))
    )
    (net (code "77") (name "unconnected-(U1-PC8-Pad39)") (class "Default")
      (node (ref "U1") (pin "39") (pinfunction "PC8_39") (pintype "input+no_connect"))
    )
    (net (code "78") (name "unconnected-(U1-PC9-Pad40)") (class "Default")
      (node (ref "U1") (pin "40") (pinfunction "PC9_40") (pintype "input+no_connect"))
    )
    (net (code "79") (name "unconnected-(U1-PC10-Pad51)") (class "Default")
      (node (ref "U1") (pin "51") (pinfunction "PC10_51") (pintype "input+no_connect"))
    )
    (net (code "80") (name "unconnected-(U1-PC12-Pad53)") (class "Default")
      (node (ref "U1") (pin "53") (pinfunction "PC12_53") (pintype "input+no_connect"))
    )
    (net (code "81") (name "unconnected-(U1-PD2-Pad54)") (class "Default")
      (node (ref "U1") (pin "54") (pinfunction "PD2_54") (pintype "input+no_connect"))
    )
    (net (code "82") (name "unconnected-(U4-NC-Pad1)") (class "Default")
      (node (ref "U4") (pin "1") (pinfunction "NC_1") (pintype "unspecified+no_connect"))
    )
    (net (code "83") (name "unconnected-(U4-NC-Pad2)") (class "Default")
      (node (ref "U4") (pin "2") (pinfunction "NC_2") (pintype "unspecified+no_connect"))
    )
    (net (code "84") (name "unconnected-(U4-NC-Pad9)") (class "Default")
      (node (ref "U4") (pin "9") (pinfunction "NC_9") (pintype "unspecified+no_connect"))
    )
    (net (code "85") (name "unconnected-(U5-CTS#-Pad9)") (class "Default")
      (node (ref "U5") (pin "9") (pinfunction "CTS#_9") (pintype "unspecified+no_connect"))
    )
    (net (code "86") (name "unconnected-(U5-DCD#-Pad12)") (class "Default")
      (node (ref "U5") (pin "12") (pinfunction "DCD#_12") (pintype "unspecified+no_connect"))
    )
    (net (code "87") (name "unconnected-(U5-DSR#-Pad10)") (class "Default")
      (node (ref "U5") (pin "10") (pinfunction "DSR#_10") (pintype "unspecified+no_connect"))
    )
    (net (code "88") (name "unconnected-(U5-DTR#-Pad13)") (class "Default")
      (node (ref "U5") (pin "13") (pinfunction "DTR#_13") (pintype "unspecified+no_connect"))
    )
    (net (code "89") (name "unconnected-(U5-NC.-Pad7)") (class "Default")
      (node (ref "U5") (pin "7") (pinfunction "NC._7") (pintype "unspecified+no_connect"))
    )
    (net (code "90") (name "unconnected-(U5-OUT#-Pad8)") (class "Default")
      (node (ref "U5") (pin "8") (pinfunction "OUT#_8") (pintype "unspecified+no_connect"))
    )
    (net (code "91") (name "unconnected-(U5-R232-Pad15)") (class "Default")
      (node (ref "U5") (pin "15") (pinfunction "R232_15") (pintype "unspecified+no_connect"))
    )
    (net (code "92") (name "unconnected-(U5-RI#-Pad11)") (class "Default")
      (node (ref "U5") (pin "11") (pinfunction "RI#_11") (pintype "unspecified+no_connect"))
    )
    (net (code "93") (name "unconnected-(U5-RTS#-Pad14)") (class "Default")
      (node (ref "U5") (pin "14") (pinfunction "RTS#_14") (pintype "unspecified+no_connect"))
    )
    (net (code "94") (name "unconnected-(U12-Pad1)") (class "Default")
      (node (ref "U12") (pin "1") (pinfunction "1_1") (pintype "unspecified"))
    )
    (net (code "95") (name "unconnected-(U12-Pad2)") (class "Default")
      (node (ref "U12") (pin "2") (pinfunction "2_2") (pintype "unspecified"))
    )
    (net (code "96") (name "unconnected-(U12-Pad3)") (class "Default")
      (node (ref "U12") (pin "3") (pinfunction "3_3") (pintype "unspecified"))
    )
    (net (code "97") (name "unconnected-(U12-Pad4)") (class "Default")
      (node (ref "U12") (pin "4") (pinfunction "4_4") (pintype "unspecified"))
    )
    (net (code "98") (name "unconnected-(U12-Pad5)") (class "Default")
      (node (ref "U12") (pin "5") (pinfunction "5_5") (pintype "unspecified"))
    )
    (net (code "99") (name "unconnected-(U12-Pad6)") (class "Default")
      (node (ref "U12") (pin "6") (pinfunction "6_6") (pintype "unspecified"))
    )
    (net (code "100") (name "unconnected-(U12-Pad7)") (class "Default")
      (node (ref "U12") (pin "7") (pinfunction "7_7") (pintype "unspecified"))
    )
    (net (code "101") (name "unconnected-(U12-Pad8)") (class "Default")
      (node (ref "U12") (pin "8") (pinfunction "8_8") (pintype "unspecified"))
    )
    (net (code "102") (name "unconnected-(U12-Pad9)") (class "Default")
      (node (ref "U12") (pin "9") (pinfunction "9_9") (pintype "unspecified"))
    )
    (net (code "103") (name "unconnected-(U12-Pad10)") (class "Default")
      (node (ref "U12") (pin "10") (pinfunction "10_10") (pintype "unspecified"))
    )
    (net (code "104") (name "unconnected-(USB1-CC1-PadA5)") (class "Default")
      (node (ref "USB1") (pin "A5") (pinfunction "CC1_A5") (pintype "unspecified+no_connect"))
    )
    (net (code "105") (name "unconnected-(USB1-CC2-PadB5)") (class "Default")
      (node (ref "USB1") (pin "B5") (pinfunction "CC2_B5") (pintype "unspecified+no_connect"))
    )
    (net (code "106") (name "unconnected-(USB2-CC1-PadA5)") (class "Default")
      (node (ref "USB2") (pin "A5") (pinfunction "CC1_A5") (pintype "unspecified+no_connect"))
    )
    (net (code "107") (name "unconnected-(USB2-CC2-PadB5)") (class "Default")
      (node (ref "USB2") (pin "B5") (pinfunction "CC2_B5") (pintype "unspecified+no_connect"))
    )
    (net (code "108") (name "unconnected-(USB2-SBU1-PadA8)") (class "Default")
      (node (ref "USB2") (pin "A8") (pinfunction "SBU1_A8") (pintype "unspecified+no_connect"))
    )
    (net (code "109") (name "unconnected-(USB2-SBU2-PadB8)") (class "Default")
      (node (ref "USB2") (pin "B8") (pinfunction "SBU2_B8") (pintype "unspecified+no_connect"))
    )
  )
)
